# SAS_Connectors.net
KiCad netlist of a schematic drawn in Altium Designer
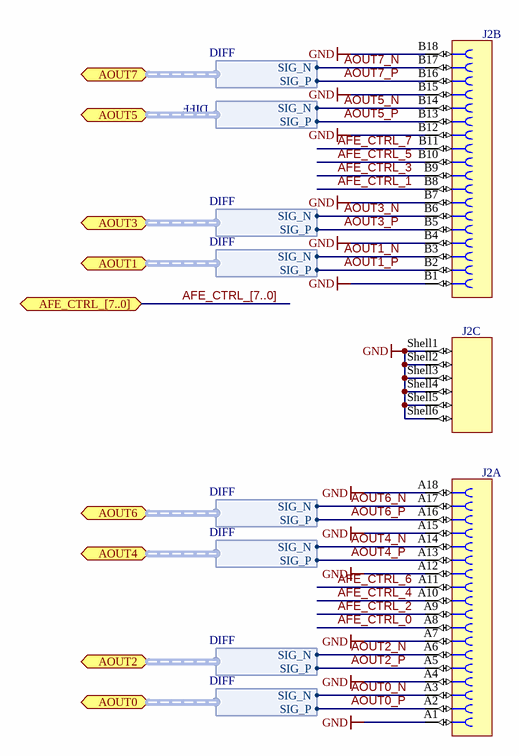
[diagram p0: SAS_Connectors.SchDoc]

(export (version "E")
  (design (tool "Eeschema 10.0.6"))
  (components
    (comp (ref "J2")
      (value "iPass™")
      (footprint "MOLEX_75783-0107")
      (fields
        (field (name "PART NUMBER") "MOLEX 75783-0107 / 75783-0136")
        (field (name "MANUFACTURER") "MOLEX")
        (field (name "MANUFACTURER PART NUMBER") "75783-0107 / 75783-0136")
        (field (name "AUTHOR") "CERN DEM JLC")
      )
      (libsource (lib "") (part "MOLEX_75783-0107_1"))
    )
  )
  (nets
    (net (code "2") (name "/AFE_CTRL_0") (class "Default")
      (node (ref "J2") (pin "A8") (pinfunction "A8_A8") (pintype "bidirectional"))
    )
    (net (code "3") (name "/AFE_CTRL_1") (class "Default")
      (node (ref "J2") (pin "B8") (pinfunction "B8_B8") (pintype "bidirectional"))
    )
    (net (code "4") (name "/AFE_CTRL_2") (class "Default")
      (node (ref "J2") (pin "A9") (pinfunction "A9_A9") (pintype "bidirectional"))
    )
    (net (code "5") (name "/AFE_CTRL_3") (class "Default")
      (node (ref "J2") (pin "B9") (pinfunction "B9_B9") (pintype "bidirectional"))
    )
    (net (code "6") (name "/AFE_CTRL_4") (class "Default")
      (node (ref "J2") (pin "A10") (pinfunction "A10_A10") (pintype "bidirectional"))
    )
    (net (code "7") (name "/AFE_CTRL_5") (class "Default")
      (node (ref "J2") (pin "B10") (pinfunction "B10_B10") (pintype "bidirectional"))
    )
    (net (code "8") (name "/AFE_CTRL_6") (class "Default")
      (node (ref "J2") (pin "A11") (pinfunction "A11_A11") (pintype "bidirectional"))
    )
    (net (code "9") (name "/AFE_CTRL_7") (class "Default")
      (node (ref "J2") (pin "B11") (pinfunction "B11_B11") (pintype "bidirectional"))
    )
    (net (code "11") (name "/AOUT0_N") (class "Default")
      (node (ref "J2") (pin "A3") (pinfunction "A3_A3") (pintype "bidirectional"))
    )
    (net (code "12") (name "/AOUT0_P") (class "Default")
      (node (ref "J2") (pin "A2") (pinfunction "A2_A2") (pintype "bidirectional"))
    )
    (net (code "13") (name "/AOUT1_N") (class "Default")
      (node (ref "J2") (pin "B3") (pinfunction "B3_B3") (pintype "bidirectional"))
    )
    (net (code "14") (name "/AOUT1_P") (class "Default")
      (node (ref "J2") (pin "B2") (pinfunction "B2_B2") (pintype "bidirectional"))
    )
    (net (code "15") (name "/AOUT2_N") (class "Default")
      (node (ref "J2") (pin "A6") (pinfunction "A6_A6") (pintype "bidirectional"))
    )
    (net (code "16") (name "/AOUT2_P") (class "Default")
      (node (ref "J2") (pin "A5") (pinfunction "A5_A5") (pintype "bidirectional"))
    )
    (net (code "17") (name "/AOUT3_N") (class "Default")
      (node (ref "J2") (pin "B6") (pinfunction "B6_B6") (pintype "bidirectional"))
    )
    (net (code "18") (name "/AOUT3_P") (class "Default")
      (node (ref "J2") (pin "B5") (pinfunction "B5_B5") (pintype "bidirectional"))
    )
    (net (code "19") (name "/AOUT4_N") (class "Default")
      (node (ref "J2") (pin "A14") (pinfunction "A14_A14") (pintype "bidirectional"))
    )
    (net (code "20") (name "/AOUT4_P") (class "Default")
      (node (ref "J2") (pin "A13") (pinfunction "A13_A13") (pintype "bidirectional"))
    )
    (net (code "21") (name "/AOUT5_N") (class "Default")
      (node (ref "J2") (pin "B14") (pinfunction "B14_B14") (pintype "bidirectional"))
    )
    (net (code "22") (name "/AOUT5_P") (class "Default")
      (node (ref "J2") (pin "B13") (pinfunction "B13_B13") (pintype "bidirectional"))
    )
    (net (code "23") (name "/AOUT6_N") (class "Default")
      (node (ref "J2") (pin "A17") (pinfunction "A17_A17") (pintype "bidirectional"))
    )
    (net (code "24") (name "/AOUT6_P") (class "Default")
      (node (ref "J2") (pin "A16") (pinfunction "A16_A16") (pintype "bidirectional"))
    )
    (net (code "25") (name "/AOUT7_N") (class "Default")
      (node (ref "J2") (pin "B17") (pinfunction "B17_B17") (pintype "bidirectional"))
    )
    (net (code "26") (name "/AOUT7_P") (class "Default")
      (node (ref "J2") (pin "B16") (pinfunction "B16_B16") (pintype "bidirectional"))
    )
    (net (code "28") (name "GND") (class "Default")
      (node (ref "J2") (pin "A1") (pinfunction "A1_A1") (pintype "bidirectional"))
      (node (ref "J2") (pin "A12") (pinfunction "A12_A12") (pintype "bidirectional"))
      (node (ref "J2") (pin "A15") (pinfunction "A15_A15") (pintype "bidirectional"))
      (node (ref "J2") (pin "A18") (pinfunction "A18_A18") (pintype "bidirectional"))
      (node (ref "J2") (pin "A4") (pinfunction "A4_A4") (pintype "bidirectional"))
      (node (ref "J2") (pin "A7") (pinfunction "A7_A7") (pintype "bidirectional"))
      (node (ref "J2") (pin "B1") (pinfunction "B1_B1") (pintype "bidirectional"))
      (node (ref "J2") (pin "B12") (pinfunction "B12_B12") (pintype "bidirectional"))
      (node (ref "J2") (pin "B15") (pinfunction "B15_B15") (pintype "bidirectional"))
      (node (ref "J2") (pin "B18") (pinfunction "B18_B18") (pintype "bidirectional"))
      (node (ref "J2") (pin "B4") (pinfunction "B4_B4") (pintype "bidirectional"))
      (node (ref "J2") (pin "B7") (pinfunction "B7_B7") (pintype "bidirectional"))
      (node (ref "J2") (pin "Shell1") (pinfunction "Shell1_Shell1") (pintype "bidirectional"))
      (node (ref "J2") (pin "Shell2") (pinfunction "Shell2_Shell2") (pintype "bidirectional"))
      (node (ref "J2") (pin "Shell3") (pinfunction "Shell3_Shell3") (pintype "bidirectional"))
      (node (ref "J2") (pin "Shell4") (pinfunction "Shell4_Shell4") (pintype "bidirectional"))
      (node (ref "J2") (pin "Shell5") (pinfunction "Shell5_Shell5") (pintype "bidirectional"))
      (node (ref "J2") (pin "Shell6") (pinfunction "Shell6_Shell6") (pintype "bidirectional"))
    )
  )
)
